# uc3843_basic.net
KiCad netlist of a schematic drawn in EAGLE
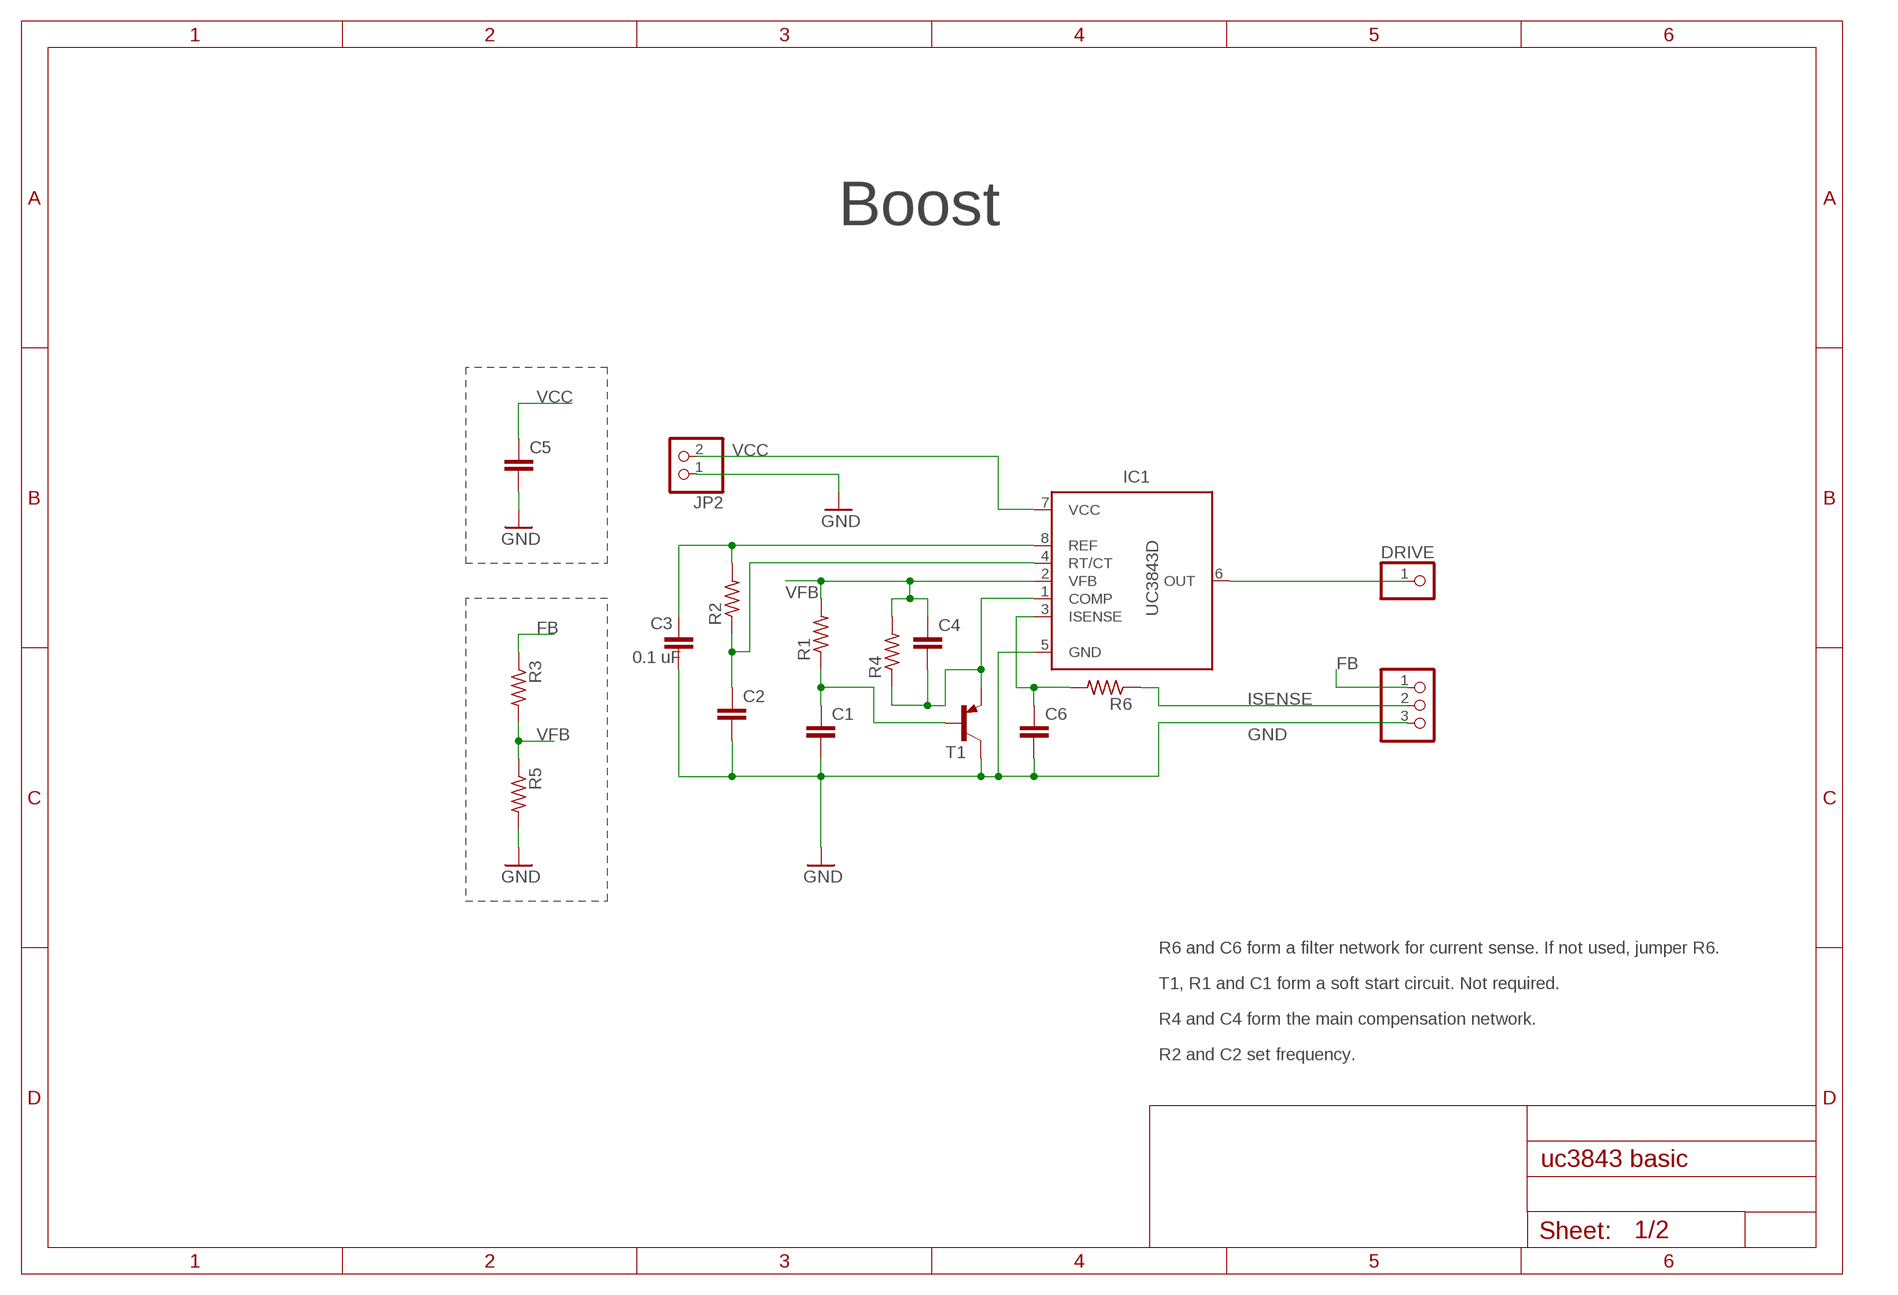
[diagram p0: schematic, sheet 1]
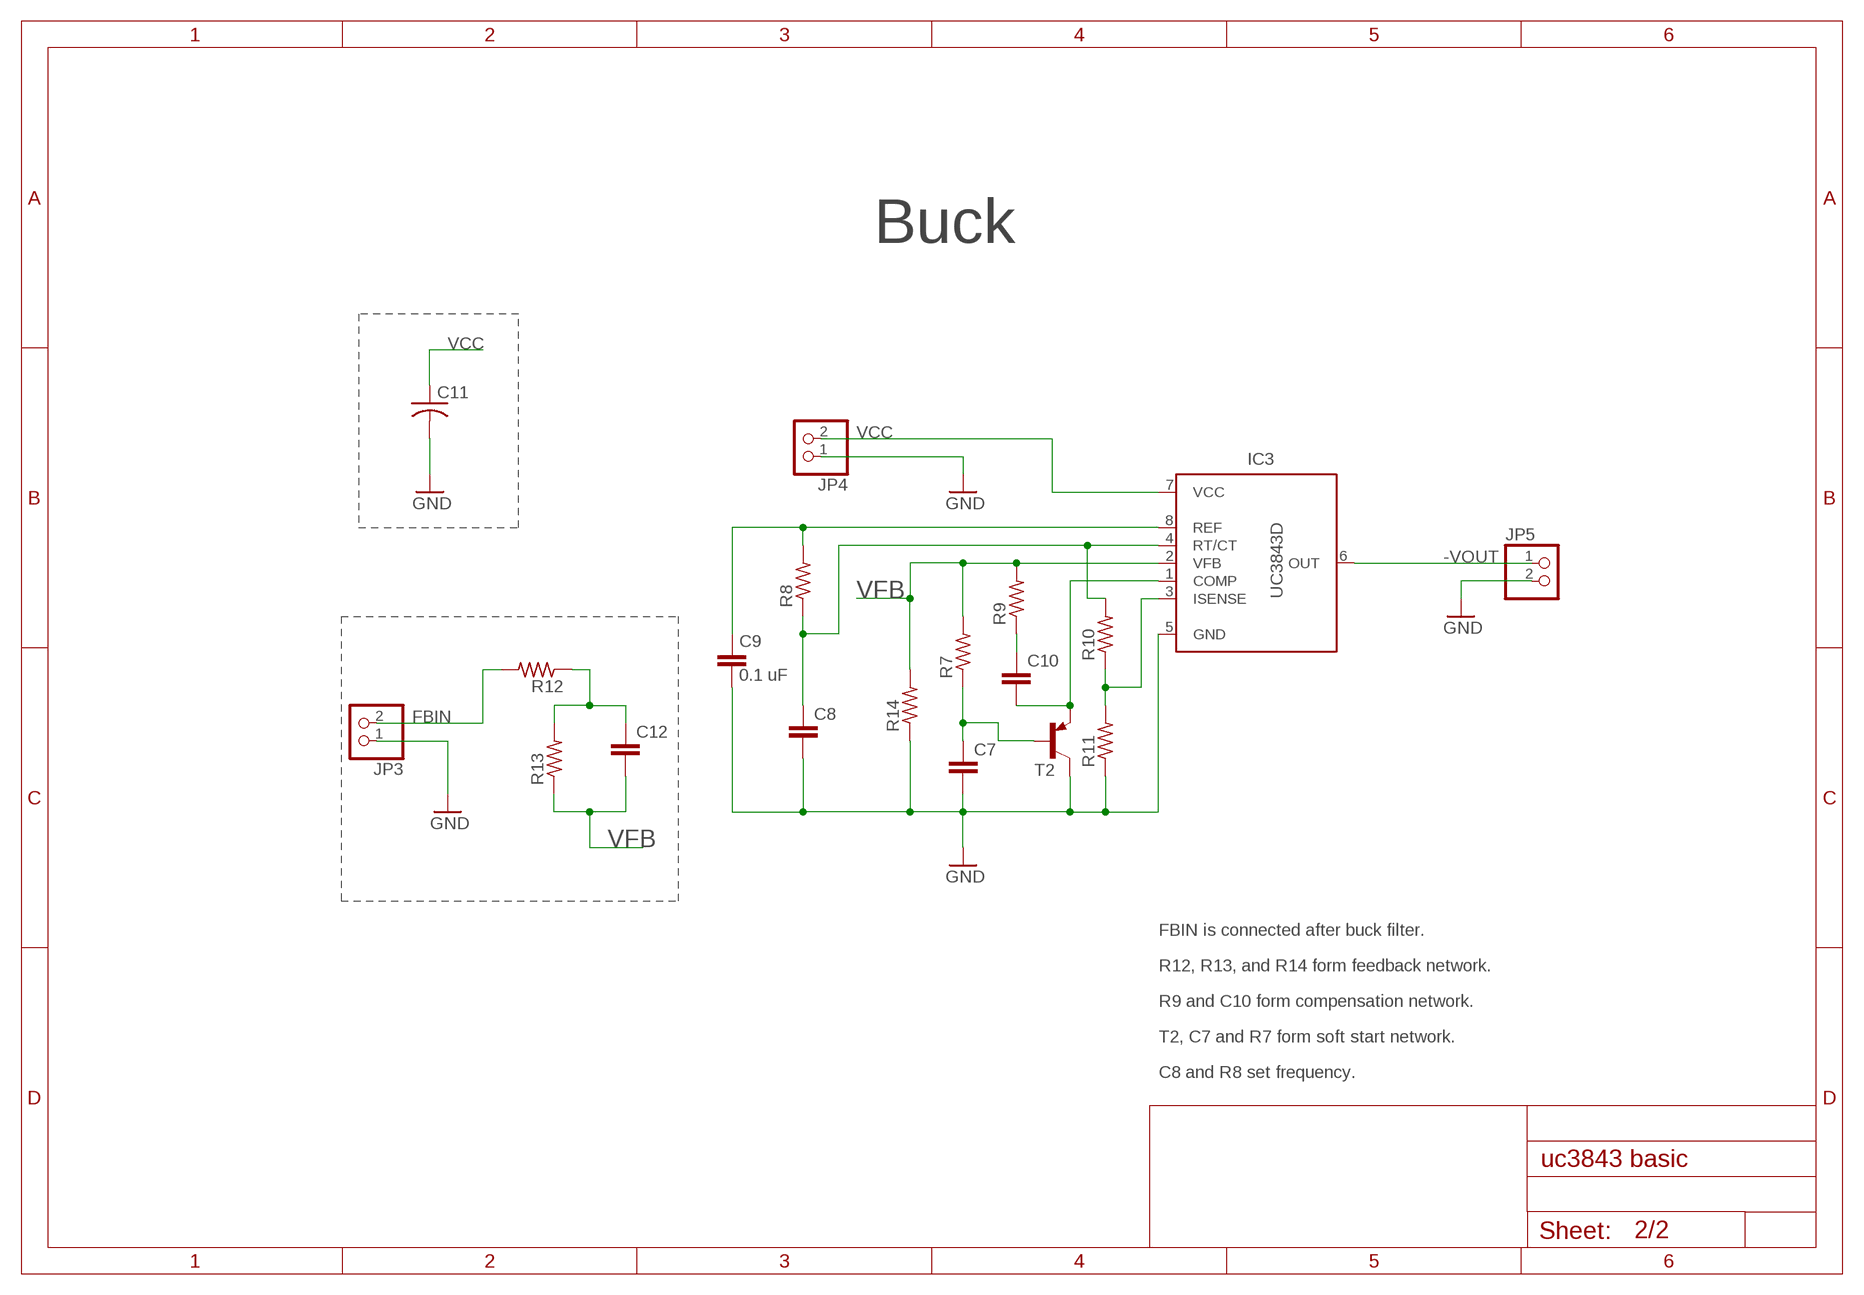
[diagram p1: schematic, sheet 2]

(export (version "E")
  (design (tool "Eeschema 10.0.6"))
  (components
    (comp (ref "C1")
      (value "C-EUC0805")
      (footprint "eagle-import:C0805")
      (libsource (lib "eagle-import") (part "C-EUC0805"))
    )
    (comp (ref "C2")
      (value "C-EUC0805")
      (footprint "eagle-import:C0805")
      (libsource (lib "eagle-import") (part "C-EUC0805"))
    )
    (comp (ref "C3")
      (value "0.1 uF")
      (footprint "eagle-import:C0805")
      (libsource (lib "eagle-import") (part "C-EUC0805"))
    )
    (comp (ref "C4")
      (value "C-EUC0805")
      (footprint "eagle-import:C0805")
      (libsource (lib "eagle-import") (part "C-EUC0805"))
    )
    (comp (ref "C5")
      (value "C-EUC0805")
      (footprint "eagle-import:C0805")
      (libsource (lib "eagle-import") (part "C-EUC0805"))
    )
    (comp (ref "C6")
      (value "C-EUC0805")
      (footprint "eagle-import:C0805")
      (libsource (lib "eagle-import") (part "C-EUC0805"))
    )
    (comp (ref "DRIVE")
      (value "PINHD-1X1")
      (footprint "eagle-import:1X01")
      (libsource (lib "eagle-import") (part "PINHD-1X1"))
    )
    (comp (ref "IC1")
      (value "UC3843D")
      (footprint "eagle-import:D_R-PDSO-G08")
      (fields (field (name "MF") "UNITRODE") (field (name "MPN") "UC3843D8"))
      (libsource (lib "eagle-import") (part "UC84?3D3"))
    )
    (comp (ref "JP1")
      (value "PINHD-1X3")
      (footprint "eagle-import:1X03")
      (libsource (lib "eagle-import") (part "PINHD-1X3"))
    )
    (comp (ref "JP2")
      (value "PINHD-1X2")
      (footprint "eagle-import:1X02")
      (libsource (lib "eagle-import") (part "PINHD-1X2"))
    )
    (comp (ref "R1")
      (value "R-US_R0805")
      (footprint "eagle-import:R0805")
      (libsource (lib "eagle-import") (part "R-US_R0805"))
    )
    (comp (ref "R2")
      (value "R-US_R0805")
      (footprint "eagle-import:R0805")
      (libsource (lib "eagle-import") (part "R-US_R0805"))
    )
    (comp (ref "R3")
      (value "R-US_R0805")
      (footprint "eagle-import:R0805")
      (libsource (lib "eagle-import") (part "R-US_R0805"))
    )
    (comp (ref "R4")
      (value "R-US_R0805")
      (footprint "eagle-import:R0805")
      (libsource (lib "eagle-import") (part "R-US_R0805"))
    )
    (comp (ref "R5")
      (value "R-US_R0805")
      (footprint "eagle-import:R0805")
      (libsource (lib "eagle-import") (part "R-US_R0805"))
    )
    (comp (ref "R6")
      (value "R-US_R0805")
      (footprint "eagle-import:R0805")
      (libsource (lib "eagle-import") (part "R-US_R0805"))
    )
    (comp (ref "T1")
      (value "-PNP-SOT23-BCE")
      (footprint "eagle-import:SOT23-BCE")
      (libsource (lib "eagle-import") (part "-PNP-SOT23-BCE"))
    )
    (comp (ref "C7")
      (value "C-EUC0805")
      (footprint "eagle-import:C0805")
      (libsource (lib "eagle-import") (part "C-EUC0805"))
    )
    (comp (ref "C8")
      (value "C-EUC0805")
      (footprint "eagle-import:C0805")
      (libsource (lib "eagle-import") (part "C-EUC0805"))
    )
    (comp (ref "C9")
      (value "0.1 uF")
      (footprint "eagle-import:C0805")
      (libsource (lib "eagle-import") (part "C-EUC0805"))
    )
    (comp (ref "C10")
      (value "C-EUC0805")
      (footprint "eagle-import:C0805")
      (libsource (lib "eagle-import") (part "C-EUC0805"))
    )
    (comp (ref "C11")
      (value "C-USC0805")
      (footprint "eagle-import:C0805")
      (libsource (lib "eagle-import") (part "C-USC0805"))
    )
    (comp (ref "C12")
      (value "C-EUC0805")
      (footprint "eagle-import:C0805")
      (libsource (lib "eagle-import") (part "C-EUC0805"))
    )
    (comp (ref "IC3")
      (value "UC3843D")
      (footprint "eagle-import:D_R-PDSO-G08")
      (fields (field (name "MF") "UNITRODE") (field (name "MPN") "UC3843D8"))
      (libsource (lib "eagle-import") (part "UC84?3D3"))
    )
    (comp (ref "JP3")
      (value "PINHD-1X2")
      (footprint "eagle-import:1X02")
      (libsource (lib "eagle-import") (part "PINHD-1X2"))
    )
    (comp (ref "JP4")
      (value "PINHD-1X2")
      (footprint "eagle-import:1X02")
      (libsource (lib "eagle-import") (part "PINHD-1X2"))
    )
    (comp (ref "JP5")
      (value "PINHD-1X2")
      (footprint "eagle-import:1X02")
      (libsource (lib "eagle-import") (part "PINHD-1X2"))
    )
    (comp (ref "R7")
      (value "R-US_R0805")
      (footprint "eagle-import:R0805")
      (libsource (lib "eagle-import") (part "R-US_R0805"))
    )
    (comp (ref "R8")
      (value "R-US_R0805")
      (footprint "eagle-import:R0805")
      (libsource (lib "eagle-import") (part "R-US_R0805"))
    )
    (comp (ref "R9")
      (value "R-US_R0805")
      (footprint "eagle-import:R0805")
      (libsource (lib "eagle-import") (part "R-US_R0805"))
    )
    (comp (ref "R10")
      (value "R-US_R0805")
      (footprint "eagle-import:R0805")
      (libsource (lib "eagle-import") (part "R-US_R0805"))
    )
    (comp (ref "R11")
      (value "R-US_R0805")
      (footprint "eagle-import:R0805")
      (libsource (lib "eagle-import") (part "R-US_R0805"))
    )
    (comp (ref "R12")
      (value "R-US_R0805")
      (footprint "eagle-import:R0805")
      (libsource (lib "eagle-import") (part "R-US_R0805"))
    )
    (comp (ref "R13")
      (value "R-US_R0805")
      (footprint "eagle-import:R0805")
      (libsource (lib "eagle-import") (part "R-US_R0805"))
    )
    (comp (ref "R14")
      (value "R-US_R0805")
      (footprint "eagle-import:R0805")
      (libsource (lib "eagle-import") (part "R-US_R0805"))
    )
    (comp (ref "T2")
      (value "-PNP-SOT23-BCE")
      (footprint "eagle-import:SOT23-BCE")
      (libsource (lib "eagle-import") (part "-PNP-SOT23-BCE"))
    )
  )
  (nets
    (net (code "1") (name "-VOUT") (class "Default")
      (node (ref "IC3") (pin "6") (pinfunction "OUT_6") (pintype "output"))
      (node (ref "JP5") (pin "1") (pinfunction "1_1") (pintype "passive"))
    )
    (net (code "2") (name "FB") (class "Default")
      (node (ref "JP1") (pin "1") (pinfunction "1_1") (pintype "passive"))
      (node (ref "R3") (pin "1") (pinfunction "1_1") (pintype "passive"))
    )
    (net (code "3") (name "FBIN") (class "Default")
      (node (ref "JP3") (pin "2") (pinfunction "2_2") (pintype "passive"))
      (node (ref "R12") (pin "2") (pinfunction "2_2") (pintype "passive"))
    )
    (net (code "4") (name "GND") (class "Default")
      (node (ref "C1") (pin "2") (pinfunction "2_2") (pintype "passive"))
      (node (ref "C11") (pin "2") (pinfunction "2_2") (pintype "passive"))
      (node (ref "C2") (pin "2") (pinfunction "2_2") (pintype "passive"))
      (node (ref "C3") (pin "2") (pinfunction "2_2") (pintype "passive"))
      (node (ref "C5") (pin "2") (pinfunction "2_2") (pintype "passive"))
      (node (ref "C6") (pin "2") (pinfunction "2_2") (pintype "passive"))
      (node (ref "C7") (pin "2") (pinfunction "2_2") (pintype "passive"))
      (node (ref "C8") (pin "2") (pinfunction "2_2") (pintype "passive"))
      (node (ref "C9") (pin "2") (pinfunction "2_2") (pintype "passive"))
      (node (ref "IC1") (pin "5") (pinfunction "GND_5") (pintype "power_in"))
      (node (ref "IC3") (pin "5") (pinfunction "GND_5") (pintype "power_in"))
      (node (ref "JP1") (pin "3") (pinfunction "3_3") (pintype "passive"))
      (node (ref "JP2") (pin "1") (pinfunction "1_1") (pintype "passive"))
      (node (ref "JP3") (pin "1") (pinfunction "1_1") (pintype "passive"))
      (node (ref "JP4") (pin "1") (pinfunction "1_1") (pintype "passive"))
      (node (ref "JP5") (pin "2") (pinfunction "2_2") (pintype "passive"))
      (node (ref "R11") (pin "1") (pinfunction "1_1") (pintype "passive"))
      (node (ref "R14") (pin "1") (pinfunction "1_1") (pintype "passive"))
      (node (ref "R5") (pin "2") (pinfunction "2_2") (pintype "passive"))
      (node (ref "T1") (pin "C") (pinfunction "C_C") (pintype "passive"))
      (node (ref "T2") (pin "C") (pinfunction "C_C") (pintype "passive"))
    )
    (net (code "5") (name "ISENSE") (class "Default")
      (node (ref "C6") (pin "1") (pinfunction "1_1") (pintype "passive"))
      (node (ref "IC1") (pin "3") (pinfunction "ISENSE_3") (pintype "input"))
      (node (ref "IC3") (pin "3") (pinfunction "ISENSE_3") (pintype "input"))
      (node (ref "R10") (pin "1") (pinfunction "1_1") (pintype "passive"))
      (node (ref "R11") (pin "2") (pinfunction "2_2") (pintype "passive"))
      (node (ref "R6") (pin "2") (pinfunction "2_2") (pintype "passive"))
    )
    (net (code "6") (name "Net-(C1-Pad1)") (class "Default")
      (node (ref "C1") (pin "1") (pinfunction "1_1") (pintype "passive"))
      (node (ref "R1") (pin "1") (pinfunction "1_1") (pintype "passive"))
      (node (ref "T1") (pin "B") (pinfunction "B_B") (pintype "passive"))
    )
    (net (code "7") (name "Net-(C7-Pad1)") (class "Default")
      (node (ref "C7") (pin "1") (pinfunction "1_1") (pintype "passive"))
      (node (ref "R7") (pin "1") (pinfunction "1_1") (pintype "passive"))
      (node (ref "T2") (pin "B") (pinfunction "B_B") (pintype "passive"))
    )
    (net (code "8") (name "Net-(C10-Pad1)") (class "Default")
      (node (ref "C10") (pin "1") (pinfunction "1_1") (pintype "passive"))
      (node (ref "R9") (pin "1") (pinfunction "1_1") (pintype "passive"))
    )
    (net (code "9") (name "Net-(C12-Pad1)") (class "Default")
      (node (ref "C12") (pin "1") (pinfunction "1_1") (pintype "passive"))
      (node (ref "R12") (pin "1") (pinfunction "1_1") (pintype "passive"))
      (node (ref "R13") (pin "2") (pinfunction "2_2") (pintype "passive"))
    )
    (net (code "10") (name "Net-(IC1-COMP)") (class "Default")
      (node (ref "C4") (pin "2") (pinfunction "2_2") (pintype "passive"))
      (node (ref "IC1") (pin "1") (pinfunction "COMP_1") (pintype "passive"))
      (node (ref "R4") (pin "1") (pinfunction "1_1") (pintype "passive"))
      (node (ref "T1") (pin "E") (pinfunction "E_E") (pintype "passive"))
    )
    (net (code "11") (name "Net-(IC1-OUT)") (class "Default")
      (node (ref "DRIVE") (pin "1") (pinfunction "1_1") (pintype "passive"))
      (node (ref "IC1") (pin "6") (pinfunction "OUT_6") (pintype "output"))
    )
    (net (code "12") (name "Net-(IC1-REF)") (class "Default")
      (node (ref "C3") (pin "1") (pinfunction "1_1") (pintype "passive"))
      (node (ref "IC1") (pin "8") (pinfunction "REF_8") (pintype "output"))
      (node (ref "R2") (pin "2") (pinfunction "2_2") (pintype "passive"))
    )
    (net (code "13") (name "Net-(IC1-RT{slash}CT)") (class "Default")
      (node (ref "C2") (pin "1") (pinfunction "1_1") (pintype "passive"))
      (node (ref "IC1") (pin "4") (pinfunction "RT/CT_4") (pintype "input"))
      (node (ref "R2") (pin "1") (pinfunction "1_1") (pintype "passive"))
    )
    (net (code "14") (name "Net-(IC3-COMP)") (class "Default")
      (node (ref "C10") (pin "2") (pinfunction "2_2") (pintype "passive"))
      (node (ref "IC3") (pin "1") (pinfunction "COMP_1") (pintype "passive"))
      (node (ref "T2") (pin "E") (pinfunction "E_E") (pintype "passive"))
    )
    (net (code "15") (name "Net-(IC3-REF)") (class "Default")
      (node (ref "C9") (pin "1") (pinfunction "1_1") (pintype "passive"))
      (node (ref "IC3") (pin "8") (pinfunction "REF_8") (pintype "output"))
      (node (ref "R8") (pin "2") (pinfunction "2_2") (pintype "passive"))
    )
    (net (code "16") (name "Net-(IC3-RT{slash}CT)") (class "Default")
      (node (ref "C8") (pin "1") (pinfunction "1_1") (pintype "passive"))
      (node (ref "IC3") (pin "4") (pinfunction "RT/CT_4") (pintype "input"))
      (node (ref "R10") (pin "2") (pinfunction "2_2") (pintype "passive"))
      (node (ref "R8") (pin "1") (pinfunction "1_1") (pintype "passive"))
    )
    (net (code "17") (name "Net-(JP1-Pad2)") (class "Default")
      (node (ref "JP1") (pin "2") (pinfunction "2_2") (pintype "passive"))
      (node (ref "R6") (pin "1") (pinfunction "1_1") (pintype "passive"))
    )
    (net (code "18") (name "VCC") (class "Default")
      (node (ref "C11") (pin "1") (pinfunction "1_1") (pintype "passive"))
      (node (ref "C5") (pin "1") (pinfunction "1_1") (pintype "passive"))
      (node (ref "IC1") (pin "7") (pinfunction "VCC_7") (pintype "power_in"))
      (node (ref "IC3") (pin "7") (pinfunction "VCC_7") (pintype "power_in"))
      (node (ref "JP2") (pin "2") (pinfunction "2_2") (pintype "passive"))
      (node (ref "JP4") (pin "2") (pinfunction "2_2") (pintype "passive"))
    )
    (net (code "19") (name "VFB") (class "Default")
      (node (ref "C12") (pin "2") (pinfunction "2_2") (pintype "passive"))
      (node (ref "C4") (pin "1") (pinfunction "1_1") (pintype "passive"))
      (node (ref "IC1") (pin "2") (pinfunction "VFB_2") (pintype "input"))
      (node (ref "IC3") (pin "2") (pinfunction "VFB_2") (pintype "input"))
      (node (ref "R1") (pin "2") (pinfunction "2_2") (pintype "passive"))
      (node (ref "R13") (pin "1") (pinfunction "1_1") (pintype "passive"))
      (node (ref "R14") (pin "2") (pinfunction "2_2") (pintype "passive"))
      (node (ref "R3") (pin "2") (pinfunction "2_2") (pintype "passive"))
      (node (ref "R4") (pin "2") (pinfunction "2_2") (pintype "passive"))
      (node (ref "R5") (pin "1") (pinfunction "1_1") (pintype "passive"))
      (node (ref "R7") (pin "2") (pinfunction "2_2") (pintype "passive"))
      (node (ref "R9") (pin "2") (pinfunction "2_2") (pintype "passive"))
    )
  )
)
